# AuxilaryWiring.net
KiCad netlist of a schematic drawn in EAGLE
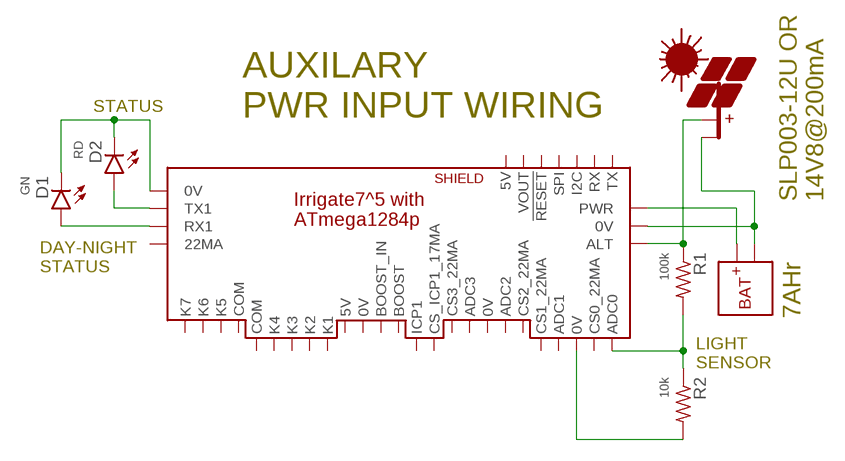
[diagram p0: schematic, sheet 1]

(export (version "E")
  (design (tool "Eeschema 10.0.6"))
  (components
    (comp (ref "D1")
      (value "GN")
      (footprint "eagle-import:LED5MM")
      (libsource (lib "eagle-import") (part "LED5MM"))
    )
    (comp (ref "D2")
      (value "RD")
      (footprint "eagle-import:LED5MM")
      (libsource (lib "eagle-import") (part "LED5MM"))
    )
    (comp (ref "PV4")
      (value "PV")
      (footprint "eagle-import:NA-30")
      (libsource (lib "eagle-import") (part "PV"))
    )
    (comp (ref "R1")
      (value "100k")
      (footprint "eagle-import:C0805(2012)")
      (libsource (lib "eagle-import") (part "R0805"))
    )
    (comp (ref "R2")
      (value "10k")
      (footprint "eagle-import:C0805(2012)")
      (libsource (lib "eagle-import") (part "R0805"))
    )
    (comp (ref "U$1")
      (value "IRRIGATE7")
      (footprint "eagle-import:WITH_RPU_NAMES")
      (libsource (lib "eagle-import") (part "IRRIGATE7"))
    )
    (comp (ref "U$7")
      (value "BAT")
      (footprint "eagle-import:NA-30")
      (libsource (lib "eagle-import") (part "BAT"))
    )
  )
  (nets
    (net (code "1") (name "Net-(D1-PadK)") (class "Default")
      (node (ref "D1") (pin "K") (pinfunction "K_K") (pintype "passive"))
      (node (ref "D2") (pin "K") (pinfunction "K_K") (pintype "passive"))
      (node (ref "U$1") (pin "17MA@ICP3") (pinfunction "0V_17MA@ICP3") (pintype "bidirectional"))
    )
    (net (code "2") (name "Net-(PV4-+PV)") (class "Default")
      (node (ref "PV4") (pin "1") (pinfunction "+PV_1") (pintype "bidirectional"))
      (node (ref "R1") (pin "1") (pinfunction "1_1") (pintype "passive"))
      (node (ref "U$1") (pin "AUX") (pinfunction "ALT_AUX") (pintype "bidirectional"))
    )
    (net (code "3") (name "Net-(PV4--PV)") (class "Default")
      (node (ref "PV4") (pin "2") (pinfunction "-PV_2") (pintype "bidirectional"))
      (node (ref "U$1") (pin "0V@PWR") (pinfunction "0V_0V@PWR") (pintype "bidirectional"))
      (node (ref "U$7") (pin "2") (pinfunction "-BAT_2") (pintype "bidirectional"))
    )
    (net (code "4") (name "Net-(R1-Pad2)") (class "Default")
      (node (ref "R1") (pin "2") (pinfunction "2_2") (pintype "passive"))
      (node (ref "R2") (pin "1") (pinfunction "1_1") (pintype "passive"))
      (node (ref "U$1") (pin "ADC0") (pinfunction "ADC0_ADC0") (pintype "bidirectional"))
    )
    (net (code "5") (name "Net-(R2-Pad2)") (class "Default")
      (node (ref "R2") (pin "2") (pinfunction "2_2") (pintype "passive"))
      (node (ref "U$1") (pin "0V@ADC2") (pinfunction "0V_0V@ADC2") (pintype "bidirectional"))
    )
    (net (code "6") (name "Net-(U$1-RX1)") (class "Default")
      (node (ref "D1") (pin "A") (pinfunction "A_A") (pintype "passive"))
      (node (ref "U$1") (pin "DIO2") (pinfunction "RX1_DIO2") (pintype "bidirectional"))
    )
    (net (code "7") (name "Net-(U$1-TX1)") (class "Default")
      (node (ref "D2") (pin "A") (pinfunction "A_A") (pintype "passive"))
      (node (ref "U$1") (pin "DIO3") (pinfunction "TX1_DIO3") (pintype "bidirectional"))
    )
    (net (code "8") (name "Net-(U$7-+BAT)") (class "Default")
      (node (ref "U$1") (pin "PWR") (pinfunction "PWR_PWR") (pintype "bidirectional"))
      (node (ref "U$7") (pin "1") (pinfunction "+BAT_1") (pintype "bidirectional"))
    )
    (net (code "9") (name "unconnected-(U$1-0V-PadICP3)") (class "Default")
      (node (ref "U$1") (pin "ICP3") (pinfunction "0V_ICP3") (pintype "bidirectional"))
    )
    (net (code "10") (name "unconnected-(U$1-5V-PadSHLD_5V)") (class "Default")
      (node (ref "U$1") (pin "SHLD_5V") (pinfunction "5V_SHLD_5V") (pintype "bidirectional"))
    )
    (net (code "11") (name "unconnected-(U$1-22MA-Pad22MA@DIO2)") (class "Default")
      (node (ref "U$1") (pin "22MA@DIO2") (pinfunction "22MA_22MA@DIO2") (pintype "bidirectional"))
    )
    (net (code "12") (name "unconnected-(U$1-ADC2-PadADC4)") (class "Default")
      (node (ref "U$1") (pin "ADC4") (pinfunction "ADC2_ADC4") (pintype "bidirectional"))
    )
    (net (code "13") (name "unconnected-(U$1-ADC3-PadADC5)") (class "Default")
      (node (ref "U$1") (pin "ADC5") (pinfunction "ADC3_ADC5") (pintype "bidirectional"))
    )
    (net (code "14") (name "unconnected-(U$1-COM-PadCOM@K4)") (class "Default")
      (node (ref "U$1") (pin "COM@K4") (pinfunction "COM_COM@K4") (pintype "bidirectional"))
    )
    (net (code "15") (name "unconnected-(U$1-COM-PadCOM@K5)") (class "Default")
      (node (ref "U$1") (pin "COM@K5") (pinfunction "COM_COM@K5") (pintype "bidirectional"))
    )
    (net (code "16") (name "unconnected-(U$1-CS0_22MA-Pad22MA@ADC0)") (class "Default")
      (node (ref "U$1") (pin "22MA@ADC0") (pinfunction "CS0_22MA_22MA@ADC0") (pintype "bidirectional"))
    )
    (net (code "17") (name "unconnected-(U$1-CS1_22MA-Pad22MA@ADC1)") (class "Default")
      (node (ref "U$1") (pin "22MA@ADC1") (pinfunction "CS1_22MA_22MA@ADC1") (pintype "bidirectional"))
    )
    (net (code "18") (name "unconnected-(U$1-CS2_22MA-Pad22MA@ADC4)") (class "Default")
      (node (ref "U$1") (pin "22MA@ADC4") (pinfunction "CS2_22MA_22MA@ADC4") (pintype "bidirectional"))
    )
    (net (code "19") (name "unconnected-(U$1-CS3_22MA-Pad22MA@ADC5)") (class "Default")
      (node (ref "U$1") (pin "22MA@ADC5") (pinfunction "CS3_22MA_22MA@ADC5") (pintype "bidirectional"))
    )
    (net (code "20") (name "unconnected-(U$1-CS_ICP1_17MA-Pad17MA@ICP1)") (class "Default")
      (node (ref "U$1") (pin "17MA@ICP1") (pinfunction "CS_ICP1_17MA_17MA@ICP1") (pintype "bidirectional"))
    )
    (net (code "21") (name "unconnected-(U$1-Pad0V)") (class "Default")
      (node (ref "U$1") (pin "0V") (pinfunction "0V_0V") (pintype "bidirectional"))
    )
    (net (code "22") (name "unconnected-(U$1-Pad5V)") (class "Default")
      (node (ref "U$1") (pin "5V") (pinfunction "5V_5V") (pintype "bidirectional"))
    )
    (net (code "23") (name "unconnected-(U$1-PadADC1)") (class "Default")
      (node (ref "U$1") (pin "ADC1") (pinfunction "ADC1_ADC1") (pintype "bidirectional"))
    )
    (net (code "24") (name "unconnected-(U$1-PadBOOST)") (class "Default")
      (node (ref "U$1") (pin "BOOST") (pinfunction "BOOST_BOOST") (pintype "bidirectional"))
    )
    (net (code "25") (name "unconnected-(U$1-PadBOOST_IN)") (class "Default")
      (node (ref "U$1") (pin "BOOST_IN") (pinfunction "BOOST_IN_BOOST_IN") (pintype "bidirectional"))
    )
    (net (code "26") (name "unconnected-(U$1-PadI2C)") (class "Default")
      (node (ref "U$1") (pin "I2C") (pinfunction "I2C_I2C") (pintype "bidirectional"))
    )
    (net (code "27") (name "unconnected-(U$1-PadICP1)") (class "Default")
      (node (ref "U$1") (pin "ICP1") (pinfunction "ICP1_ICP1") (pintype "bidirectional"))
    )
    (net (code "28") (name "unconnected-(U$1-PadK1)") (class "Default")
      (node (ref "U$1") (pin "K1") (pinfunction "K1_K1") (pintype "bidirectional"))
    )
    (net (code "29") (name "unconnected-(U$1-PadK2)") (class "Default")
      (node (ref "U$1") (pin "K2") (pinfunction "K2_K2") (pintype "bidirectional"))
    )
    (net (code "30") (name "unconnected-(U$1-PadK3)") (class "Default")
      (node (ref "U$1") (pin "K3") (pinfunction "K3_K3") (pintype "bidirectional"))
    )
    (net (code "31") (name "unconnected-(U$1-PadK4)") (class "Default")
      (node (ref "U$1") (pin "K4") (pinfunction "K4_K4") (pintype "bidirectional"))
    )
    (net (code "32") (name "unconnected-(U$1-PadK5)") (class "Default")
      (node (ref "U$1") (pin "K5") (pinfunction "K5_K5") (pintype "bidirectional"))
    )
    (net (code "33") (name "unconnected-(U$1-PadK6)") (class "Default")
      (node (ref "U$1") (pin "K6") (pinfunction "K6_K6") (pintype "bidirectional"))
    )
    (net (code "34") (name "unconnected-(U$1-PadK7)") (class "Default")
      (node (ref "U$1") (pin "K7") (pinfunction "K7_K7") (pintype "bidirectional"))
    )
    (net (code "35") (name "unconnected-(U$1-PadRX)") (class "Default")
      (node (ref "U$1") (pin "RX") (pinfunction "RX_RX") (pintype "bidirectional"))
    )
    (net (code "36") (name "unconnected-(U$1-PadSPI)") (class "Default")
      (node (ref "U$1") (pin "SPI") (pinfunction "SPI_SPI") (pintype "bidirectional"))
    )
    (net (code "37") (name "unconnected-(U$1-PadTX)") (class "Default")
      (node (ref "U$1") (pin "TX") (pinfunction "TX_TX") (pintype "bidirectional"))
    )
    (net (code "38") (name "unconnected-(U$1-VOUT-PadSHLD_VOUT)") (class "Default")
      (node (ref "U$1") (pin "SHLD_VOUT") (pinfunction "VOUT_SHLD_VOUT") (pintype "bidirectional"))
    )
    (net (code "39") (name "unconnected-(U$1-~{RESET}-Pad!RESET)") (class "Default")
      (node (ref "U$1") (pin "!RESET") (pinfunction "~{RESET}_!RESET") (pintype "bidirectional"))
    )
  )
)
